# Top_Board_V2.net
KiCad netlist of a schematic drawn in EasyEDA
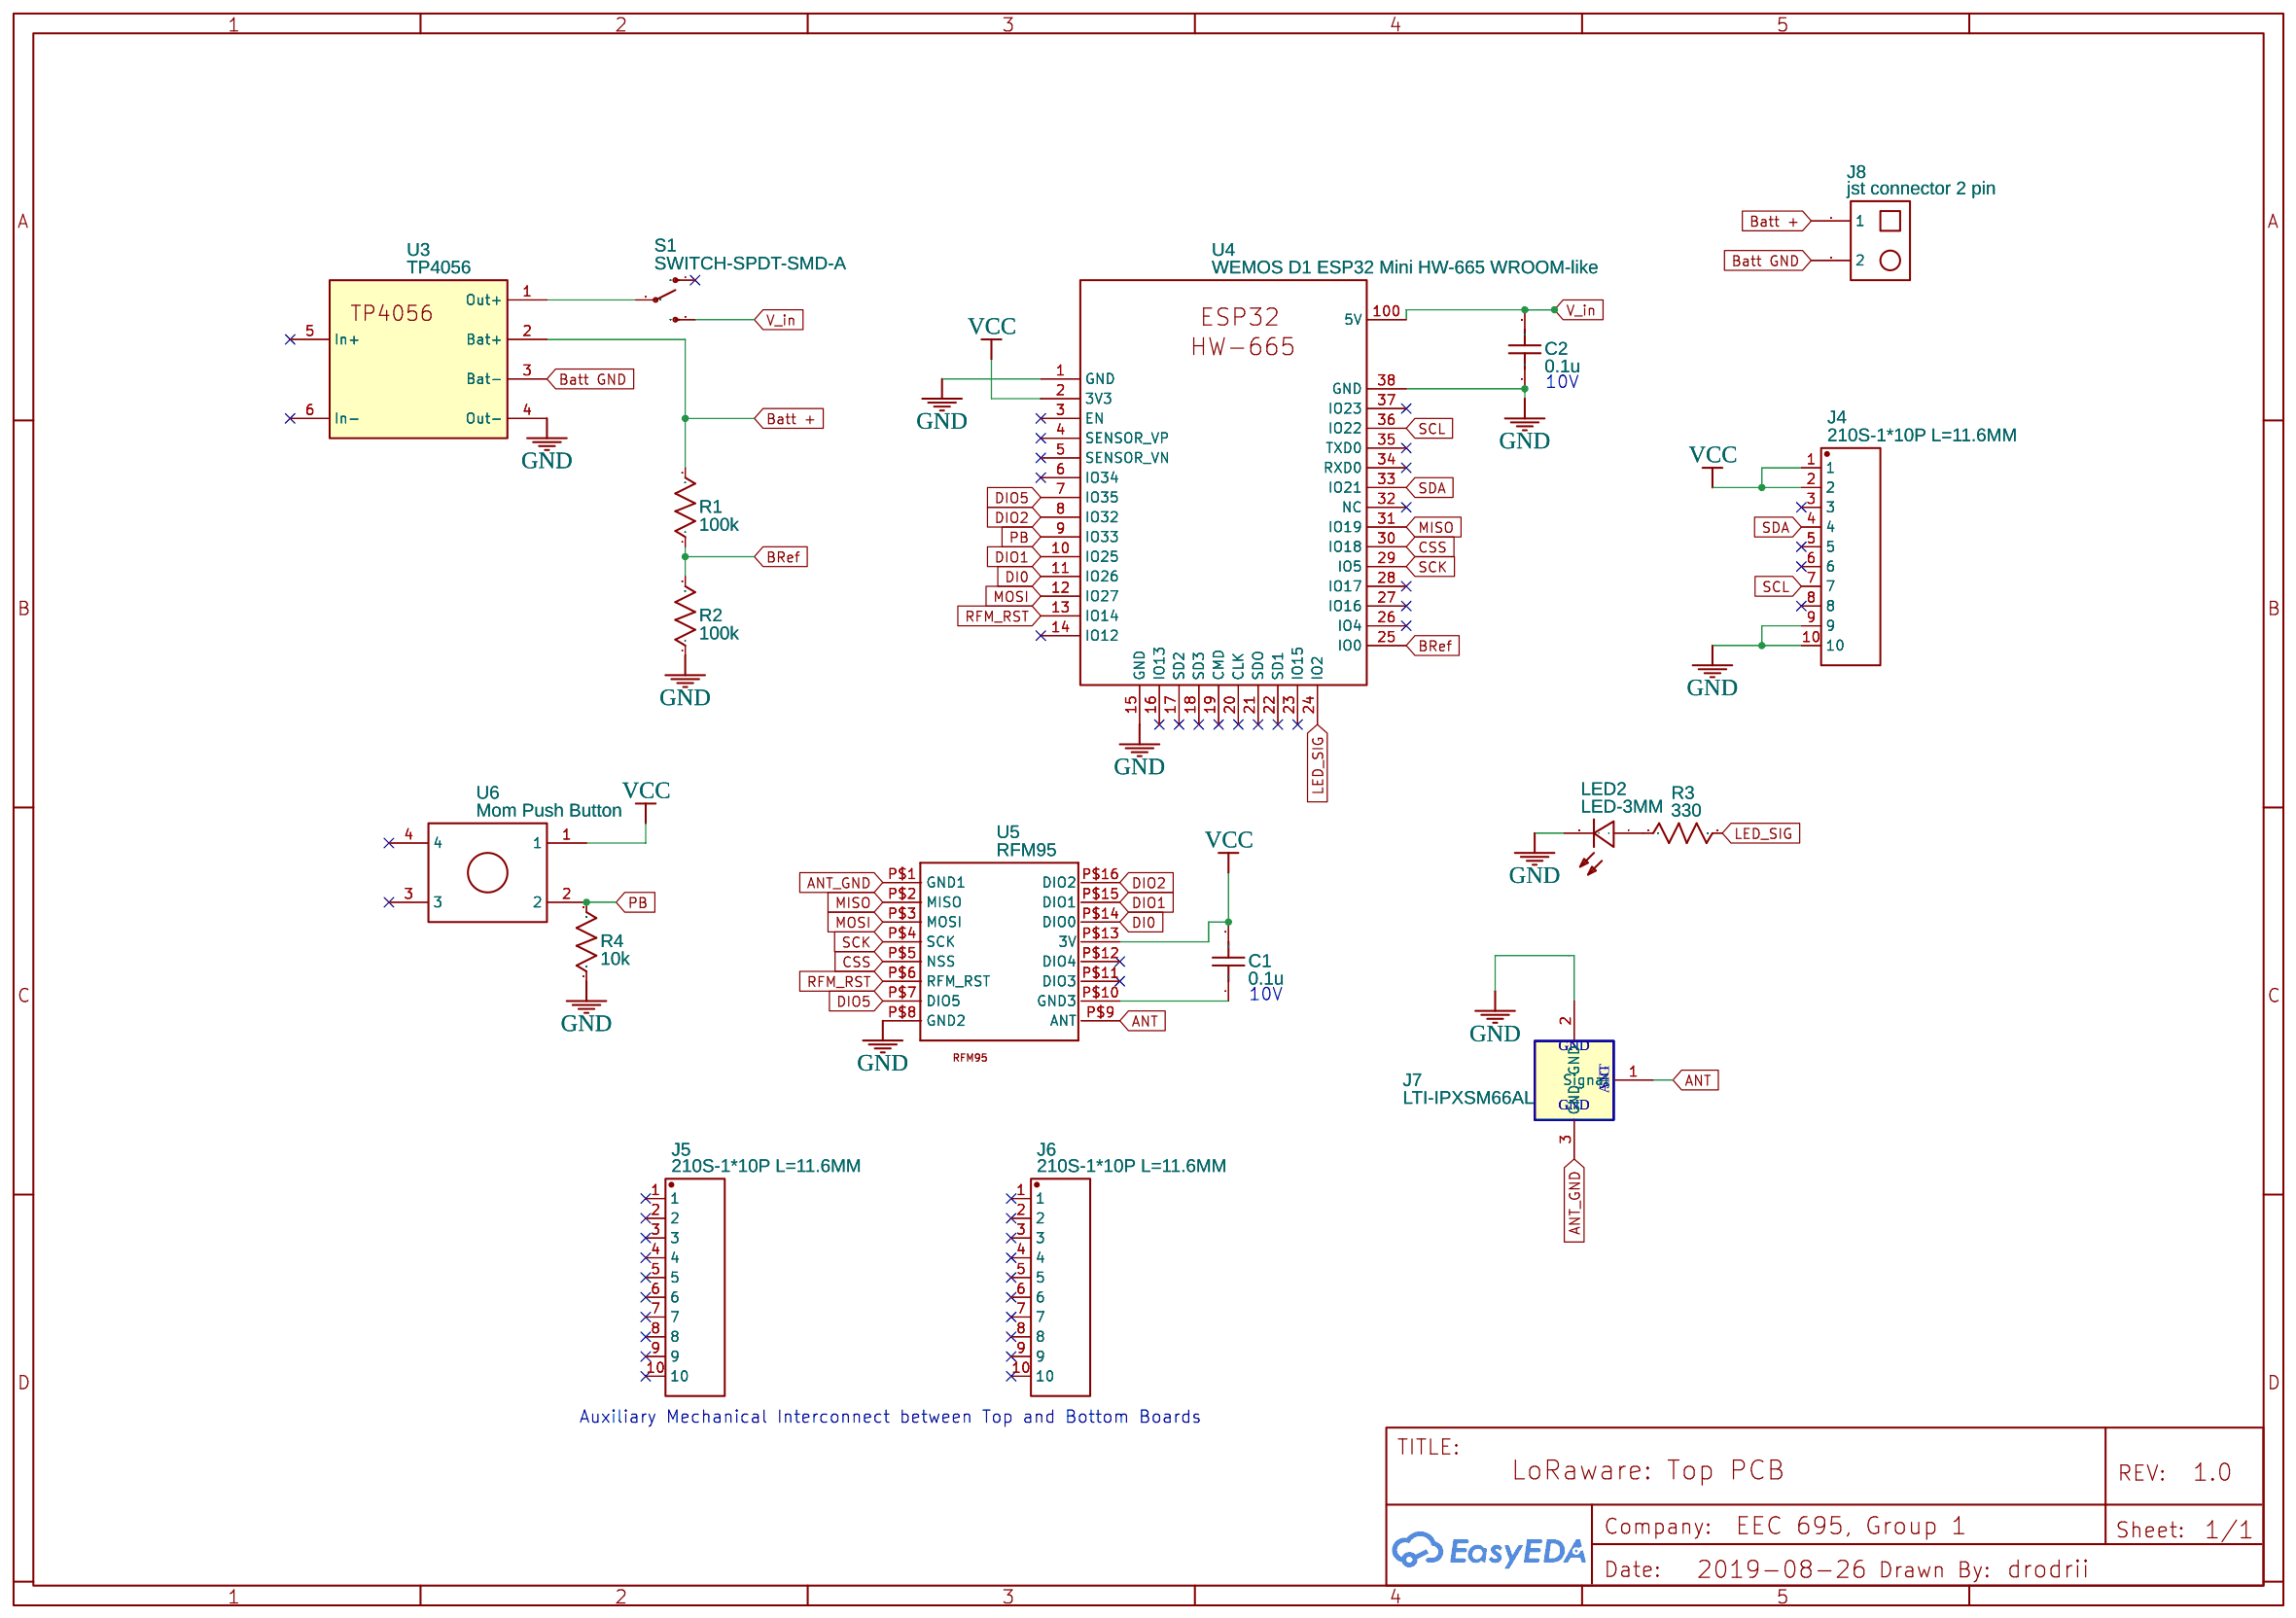
[diagram p0: schematic sheet]

(export (version "E")
  (design (tool "Eeschema 10.0.6"))
  (components
    (comp (ref "C1") (value "0.1u") (libsource (lib "") (part "Cap_0805_US")))
    (comp (ref "C2") (value "0.1u") (libsource (lib "") (part "Cap_0805_US")))
    (comp (ref "J4")
      (value "210S-1*10P L=11.6MM")
      (fields
        (field (name "BOM_Manufacturer Part") "210S-1*10P L=11.6MMGold-plated black")
        (field (name "BOM_Supplier Part") "C124372")
      )
      (libsource (lib "") (part "Unknown_925_275"))
    )
    (comp (ref "J5")
      (value "210S-1*10P L=11.6MM")
      (fields
        (field (name "BOM_Manufacturer Part") "210S-1*10P L=11.6MMGold-plated black")
        (field (name "BOM_Supplier Part") "C124372")
      )
      (libsource (lib "") (part "Unknown_340_645"))
    )
    (comp (ref "J6")
      (value "210S-1*10P L=11.6MM")
      (fields
        (field (name "BOM_Manufacturer Part") "210S-1*10P L=11.6MMGold-plated black")
        (field (name "BOM_Supplier Part") "C124372")
      )
      (libsource (lib "") (part "Unknown_525_645"))
    )
    (comp (ref "J7") (value "LTI-IPXSM66AL") (libsource (lib "") (part "Unknown_790_540")))
    (comp (ref "J8")
      (value "jst connector 2 pin")
      (fields (field (name "BOM_Manufacturer Part") "JST_XH CONNECTOR"))
      (libsource (lib "") (part "Unknown_940_115"))
    )
    (comp (ref "LED2")
      (value "LED-3MM")
      (fields
        (field (name "BOM_Manufacturer Part") "204-10SURD/S530-A3")
        (field (name "BOM_Supplier Part") "C99772")
      )
      (libsource (lib "") (part "Unknown_805_420"))
    )
    (comp (ref "R1")
      (value "100k")
      (fields (field (name "BOM_Manufacturer Part") "?"))
      (libsource (lib "") (part "Res_0805(1/8W)_US_1"))
    )
    (comp (ref "R2")
      (value "100k")
      (fields (field (name "BOM_Manufacturer Part") "?"))
      (libsource (lib "") (part "Res_0805(1/8W)_US_1"))
    )
    (comp (ref "R3")
      (value "330")
      (fields (field (name "BOM_Manufacturer Part") "?"))
      (libsource (lib "") (part "Res_0805(1/8W)_US"))
    )
    (comp (ref "R4")
      (value "10k")
      (fields (field (name "BOM_Manufacturer Part") "?"))
      (libsource (lib "") (part "Res_0805(1/8W)_US_1"))
    )
    (comp (ref "S1")
      (value "SWITCH-SPDT-SMD-A")
      (fields (field (name "BOM_Manufacturer Part") "?"))
      (libsource (lib "") (part "Unknown_330_145"))
    )
    (comp (ref "U3") (value "TP4056") (libsource (lib "") (part "Unknown_160_215")))
    (comp (ref "U4")
      (value "WEMOS D1 ESP32 Mini HW-665 WROOM-like")
      (fields (field (name "BOM_Supplier Part") "WEMOS_D1_ESP32"))
      (libsource (lib "") (part "Unknown_540_325"))
    )
    (comp (ref "U5") (value "RFM95") (libsource (lib "") (part "Unknown_500_485")))
    (comp (ref "U6")
      (value "Mom Push Button")
      (fields (field (name "BOM_Manufacturer Part") "Momentary Push Button"))
      (libsource (lib "") (part "Unknown_270_410"))
    )
  )
  (nets
    (net (code "1") (name "ANT") (class "Default")
      (node (ref "J7") (pin "1") (pinfunction "Signal_1") (pintype "input"))
      (node (ref "U5") (pin "P$9") (pinfunction "ANT_P$9") (pintype "bidirectional"))
    )
    (net (code "2") (name "ANT_GND") (class "Default")
      (node (ref "J7") (pin "3") (pinfunction "GND_3") (pintype "unspecified"))
      (node (ref "U5") (pin "P$1") (pinfunction "GND1_P$1") (pintype "bidirectional"))
    )
    (net (code "3") (name "BRef") (class "Default")
      (node (ref "R1") (pin "1") (pinfunction "1_1") (pintype "unspecified"))
      (node (ref "R2") (pin "2") (pinfunction "2_2") (pintype "unspecified"))
      (node (ref "U4") (pin "25") (pinfunction "IO0_25") (pintype "bidirectional"))
    )
    (net (code "4") (name "Batt +") (class "Default")
      (node (ref "J8") (pin "1") (pinfunction "1_1") (pintype "unspecified"))
      (node (ref "R1") (pin "2") (pinfunction "2_2") (pintype "unspecified"))
      (node (ref "U3") (pin "2") (pinfunction "Bat+_2") (pintype "unspecified"))
    )
    (net (code "5") (name "Batt GND") (class "Default")
      (node (ref "J8") (pin "2") (pinfunction "2_2") (pintype "unspecified"))
      (node (ref "U3") (pin "3") (pinfunction "Bat-_3") (pintype "unspecified"))
    )
    (net (code "6") (name "CSS") (class "Default")
      (node (ref "U4") (pin "30") (pinfunction "IO18_30") (pintype "input"))
      (node (ref "U5") (pin "P$5") (pinfunction "NSS_P$5") (pintype "bidirectional"))
    )
    (net (code "7") (name "DI0") (class "Default")
      (node (ref "U4") (pin "11") (pinfunction "IO26_11") (pintype "bidirectional"))
      (node (ref "U5") (pin "P$14") (pinfunction "DIO0_P$14") (pintype "bidirectional"))
    )
    (net (code "8") (name "DIO1") (class "Default")
      (node (ref "U4") (pin "10") (pinfunction "IO25_10") (pintype "bidirectional"))
      (node (ref "U5") (pin "P$15") (pinfunction "DIO1_P$15") (pintype "bidirectional"))
    )
    (net (code "9") (name "DIO2") (class "Default")
      (node (ref "U4") (pin "8") (pinfunction "IO32_8") (pintype "bidirectional"))
      (node (ref "U5") (pin "P$16") (pinfunction "DIO2_P$16") (pintype "bidirectional"))
    )
    (net (code "10") (name "DIO5") (class "Default")
      (node (ref "U4") (pin "7") (pinfunction "IO35_7") (pintype "bidirectional"))
      (node (ref "U5") (pin "P$7") (pinfunction "DIO5_P$7") (pintype "bidirectional"))
    )
    (net (code "11") (name "GND") (class "Default")
      (node (ref "C2") (pin "1") (pinfunction "1_1") (pintype "unspecified"))
      (node (ref "J4") (pin "10") (pinfunction "10_10") (pintype "unspecified"))
      (node (ref "J4") (pin "9") (pinfunction "9_9") (pintype "unspecified"))
      (node (ref "J7") (pin "2") (pinfunction "GND_2") (pintype "unspecified"))
      (node (ref "LED2") (pin "2") (pinfunction "-_2") (pintype "unspecified"))
      (node (ref "R2") (pin "1") (pinfunction "1_1") (pintype "unspecified"))
      (node (ref "R4") (pin "1") (pinfunction "1_1") (pintype "unspecified"))
      (node (ref "U3") (pin "4") (pinfunction "Out-_4") (pintype "unspecified"))
      (node (ref "U4") (pin "1") (pinfunction "GND_1") (pintype "bidirectional"))
      (node (ref "U4") (pin "15") (pinfunction "GND_15") (pintype "bidirectional"))
      (node (ref "U4") (pin "38") (pinfunction "GND_38") (pintype "bidirectional"))
      (node (ref "U5") (pin "P$8") (pinfunction "GND2_P$8") (pintype "bidirectional"))
    )
    (net (code "12") (name "LED_SIG") (class "Default")
      (node (ref "R3") (pin "2") (pinfunction "2_2") (pintype "unspecified"))
      (node (ref "U4") (pin "24") (pinfunction "IO2_24") (pintype "bidirectional"))
    )
    (net (code "13") (name "MISO") (class "Default")
      (node (ref "U4") (pin "31") (pinfunction "IO19_31") (pintype "bidirectional"))
      (node (ref "U5") (pin "P$2") (pinfunction "MISO_P$2") (pintype "bidirectional"))
    )
    (net (code "14") (name "MOSI") (class "Default")
      (node (ref "U4") (pin "12") (pinfunction "IO27_12") (pintype "bidirectional"))
      (node (ref "U5") (pin "P$3") (pinfunction "MOSI_P$3") (pintype "bidirectional"))
    )
    (net (code "15") (name "Net-(LED2-+)") (class "Default")
      (node (ref "LED2") (pin "1") (pinfunction "+_1") (pintype "unspecified"))
      (node (ref "R3") (pin "1") (pinfunction "1_1") (pintype "unspecified"))
    )
    (net (code "16") (name "Net-(S1-P)") (class "Default")
      (node (ref "S1") (pin "2") (pinfunction "P_2") (pintype "unspecified"))
      (node (ref "U3") (pin "1") (pinfunction "Out+_1") (pintype "unspecified"))
    )
    (net (code "17") (name "Net-(U5-GND3)") (class "Default")
      (node (ref "C1") (pin "1") (pinfunction "1_1") (pintype "unspecified"))
      (node (ref "U5") (pin "P$10") (pinfunction "GND3_P$10") (pintype "bidirectional"))
    )
    (net (code "18") (name "PB") (class "Default")
      (node (ref "R4") (pin "2") (pinfunction "2_2") (pintype "unspecified"))
      (node (ref "U4") (pin "9") (pinfunction "IO33_9") (pintype "bidirectional"))
      (node (ref "U6") (pin "2") (pinfunction "2_2") (pintype "unspecified"))
    )
    (net (code "19") (name "RFM_RST") (class "Default")
      (node (ref "U4") (pin "13") (pinfunction "IO14_13") (pintype "bidirectional"))
      (node (ref "U5") (pin "P$6") (pinfunction "RFM_RST_P$6") (pintype "bidirectional"))
    )
    (net (code "20") (name "SCK") (class "Default")
      (node (ref "U4") (pin "29") (pinfunction "IO5_29") (pintype "bidirectional"))
      (node (ref "U5") (pin "P$4") (pinfunction "SCK_P$4") (pintype "bidirectional"))
    )
    (net (code "21") (name "SCL") (class "Default")
      (node (ref "J4") (pin "7") (pinfunction "7_7") (pintype "unspecified"))
      (node (ref "U4") (pin "36") (pinfunction "IO22_36") (pintype "bidirectional"))
    )
    (net (code "22") (name "SDA") (class "Default")
      (node (ref "J4") (pin "4") (pinfunction "4_4") (pintype "unspecified"))
      (node (ref "U4") (pin "33") (pinfunction "IO21_33") (pintype "bidirectional"))
    )
    (net (code "23") (name "VCC") (class "Default")
      (node (ref "C1") (pin "2") (pinfunction "2_2") (pintype "unspecified"))
      (node (ref "J4") (pin "1") (pinfunction "1_1") (pintype "unspecified"))
      (node (ref "J4") (pin "2") (pinfunction "2_2") (pintype "unspecified"))
      (node (ref "U4") (pin "2") (pinfunction "3V3_2") (pintype "bidirectional"))
      (node (ref "U5") (pin "P$13") (pinfunction "3V_P$13") (pintype "bidirectional"))
      (node (ref "U6") (pin "1") (pinfunction "1_1") (pintype "unspecified"))
    )
    (net (code "24") (name "V_in") (class "Default")
      (node (ref "C2") (pin "2") (pinfunction "2_2") (pintype "unspecified"))
      (node (ref "S1") (pin "3") (pinfunction "S_3") (pintype "unspecified"))
      (node (ref "U4") (pin "100") (pinfunction "5V_100") (pintype "bidirectional"))
    )
    (net (code "25") (name "unconnected-(J4-Pad3)") (class "Default")
      (node (ref "J4") (pin "3") (pinfunction "3_3") (pintype "unspecified+no_connect"))
    )
    (net (code "26") (name "unconnected-(J4-Pad5)") (class "Default")
      (node (ref "J4") (pin "5") (pinfunction "5_5") (pintype "unspecified+no_connect"))
    )
    (net (code "27") (name "unconnected-(J4-Pad6)") (class "Default")
      (node (ref "J4") (pin "6") (pinfunction "6_6") (pintype "unspecified+no_connect"))
    )
    (net (code "28") (name "unconnected-(J4-Pad8)") (class "Default")
      (node (ref "J4") (pin "8") (pinfunction "8_8") (pintype "unspecified+no_connect"))
    )
    (net (code "29") (name "unconnected-(J5-Pad1)") (class "Default")
      (node (ref "J5") (pin "1") (pinfunction "1_1") (pintype "unspecified+no_connect"))
    )
    (net (code "30") (name "unconnected-(J5-Pad2)") (class "Default")
      (node (ref "J5") (pin "2") (pinfunction "2_2") (pintype "unspecified+no_connect"))
    )
    (net (code "31") (name "unconnected-(J5-Pad3)") (class "Default")
      (node (ref "J5") (pin "3") (pinfunction "3_3") (pintype "unspecified+no_connect"))
    )
    (net (code "32") (name "unconnected-(J5-Pad4)") (class "Default")
      (node (ref "J5") (pin "4") (pinfunction "4_4") (pintype "unspecified+no_connect"))
    )
    (net (code "33") (name "unconnected-(J5-Pad5)") (class "Default")
      (node (ref "J5") (pin "5") (pinfunction "5_5") (pintype "unspecified+no_connect"))
    )
    (net (code "34") (name "unconnected-(J5-Pad6)") (class "Default")
      (node (ref "J5") (pin "6") (pinfunction "6_6") (pintype "unspecified+no_connect"))
    )
    (net (code "35") (name "unconnected-(J5-Pad7)") (class "Default")
      (node (ref "J5") (pin "7") (pinfunction "7_7") (pintype "unspecified+no_connect"))
    )
    (net (code "36") (name "unconnected-(J5-Pad8)") (class "Default")
      (node (ref "J5") (pin "8") (pinfunction "8_8") (pintype "unspecified+no_connect"))
    )
    (net (code "37") (name "unconnected-(J5-Pad9)") (class "Default")
      (node (ref "J5") (pin "9") (pinfunction "9_9") (pintype "unspecified+no_connect"))
    )
    (net (code "38") (name "unconnected-(J5-Pad10)") (class "Default")
      (node (ref "J5") (pin "10") (pinfunction "10_10") (pintype "unspecified+no_connect"))
    )
    (net (code "39") (name "unconnected-(J6-Pad1)") (class "Default")
      (node (ref "J6") (pin "1") (pinfunction "1_1") (pintype "unspecified+no_connect"))
    )
    (net (code "40") (name "unconnected-(J6-Pad2)") (class "Default")
      (node (ref "J6") (pin "2") (pinfunction "2_2") (pintype "unspecified+no_connect"))
    )
    (net (code "41") (name "unconnected-(J6-Pad3)") (class "Default")
      (node (ref "J6") (pin "3") (pinfunction "3_3") (pintype "unspecified+no_connect"))
    )
    (net (code "42") (name "unconnected-(J6-Pad4)") (class "Default")
      (node (ref "J6") (pin "4") (pinfunction "4_4") (pintype "unspecified+no_connect"))
    )
    (net (code "43") (name "unconnected-(J6-Pad5)") (class "Default")
      (node (ref "J6") (pin "5") (pinfunction "5_5") (pintype "unspecified+no_connect"))
    )
    (net (code "44") (name "unconnected-(J6-Pad6)") (class "Default")
      (node (ref "J6") (pin "6") (pinfunction "6_6") (pintype "unspecified+no_connect"))
    )
    (net (code "45") (name "unconnected-(J6-Pad7)") (class "Default")
      (node (ref "J6") (pin "7") (pinfunction "7_7") (pintype "unspecified+no_connect"))
    )
    (net (code "46") (name "unconnected-(J6-Pad8)") (class "Default")
      (node (ref "J6") (pin "8") (pinfunction "8_8") (pintype "unspecified+no_connect"))
    )
    (net (code "47") (name "unconnected-(J6-Pad9)") (class "Default")
      (node (ref "J6") (pin "9") (pinfunction "9_9") (pintype "unspecified+no_connect"))
    )
    (net (code "48") (name "unconnected-(J6-Pad10)") (class "Default")
      (node (ref "J6") (pin "10") (pinfunction "10_10") (pintype "unspecified+no_connect"))
    )
    (net (code "49") (name "unconnected-(S1-O-Pad1)") (class "Default")
      (node (ref "S1") (pin "1") (pinfunction "O_1") (pintype "unspecified+no_connect"))
    )
    (net (code "50") (name "unconnected-(U3-In+-Pad5)") (class "Default")
      (node (ref "U3") (pin "5") (pinfunction "In+_5") (pintype "unspecified+no_connect"))
    )
    (net (code "51") (name "unconnected-(U3-In--Pad6)") (class "Default")
      (node (ref "U3") (pin "6") (pinfunction "In-_6") (pintype "unspecified+no_connect"))
    )
    (net (code "52") (name "unconnected-(U4-CLK-Pad20)") (class "Default")
      (node (ref "U4") (pin "20") (pinfunction "CLK_20") (pintype "input+no_connect"))
    )
    (net (code "53") (name "unconnected-(U4-CMD-Pad19)") (class "Default")
      (node (ref "U4") (pin "19") (pinfunction "CMD_19") (pintype "bidirectional+no_connect"))
    )
    (net (code "54") (name "unconnected-(U4-EN-Pad3)") (class "Default")
      (node (ref "U4") (pin "3") (pinfunction "EN_3") (pintype "input+no_connect"))
    )
    (net (code "55") (name "unconnected-(U4-IO4-Pad26)") (class "Default")
      (node (ref "U4") (pin "26") (pinfunction "IO4_26") (pintype "input+no_connect"))
    )
    (net (code "56") (name "unconnected-(U4-IO12-Pad14)") (class "Default")
      (node (ref "U4") (pin "14") (pinfunction "IO12_14") (pintype "bidirectional+no_connect"))
    )
    (net (code "57") (name "unconnected-(U4-IO13-Pad16)") (class "Default")
      (node (ref "U4") (pin "16") (pinfunction "IO13_16") (pintype "bidirectional+no_connect"))
    )
    (net (code "58") (name "unconnected-(U4-IO15-Pad23)") (class "Default")
      (node (ref "U4") (pin "23") (pinfunction "IO15_23") (pintype "bidirectional+no_connect"))
    )
    (net (code "59") (name "unconnected-(U4-IO16-Pad27)") (class "Default")
      (node (ref "U4") (pin "27") (pinfunction "IO16_27") (pintype "bidirectional+no_connect"))
    )
    (net (code "60") (name "unconnected-(U4-IO17-Pad28)") (class "Default")
      (node (ref "U4") (pin "28") (pinfunction "IO17_28") (pintype "bidirectional+no_connect"))
    )
    (net (code "61") (name "unconnected-(U4-IO23-Pad37)") (class "Default")
      (node (ref "U4") (pin "37") (pinfunction "IO23_37") (pintype "bidirectional+no_connect"))
    )
    (net (code "62") (name "unconnected-(U4-IO34-Pad6)") (class "Default")
      (node (ref "U4") (pin "6") (pinfunction "IO34_6") (pintype "bidirectional+no_connect"))
    )
    (net (code "63") (name "unconnected-(U4-NC-Pad32)") (class "Default")
      (node (ref "U4") (pin "32") (pinfunction "NC_32") (pintype "bidirectional+no_connect"))
    )
    (net (code "64") (name "unconnected-(U4-RXD0-Pad34)") (class "Default")
      (node (ref "U4") (pin "34") (pinfunction "RXD0_34") (pintype "bidirectional+no_connect"))
    )
    (net (code "65") (name "unconnected-(U4-SD1-Pad22)") (class "Default")
      (node (ref "U4") (pin "22") (pinfunction "SD1_22") (pintype "bidirectional+no_connect"))
    )
    (net (code "66") (name "unconnected-(U4-SD2-Pad17)") (class "Default")
      (node (ref "U4") (pin "17") (pinfunction "SD2_17") (pintype "bidirectional+no_connect"))
    )
    (net (code "67") (name "unconnected-(U4-SD3-Pad18)") (class "Default")
      (node (ref "U4") (pin "18") (pinfunction "SD3_18") (pintype "bidirectional+no_connect"))
    )
    (net (code "68") (name "unconnected-(U4-SDO-Pad21)") (class "Default")
      (node (ref "U4") (pin "21") (pinfunction "SDO_21") (pintype "bidirectional+no_connect"))
    )
    (net (code "69") (name "unconnected-(U4-SENSOR_VN-Pad5)") (class "Default")
      (node (ref "U4") (pin "5") (pinfunction "SENSOR_VN_5") (pintype "input+no_connect"))
    )
    (net (code "70") (name "unconnected-(U4-SENSOR_VP-Pad4)") (class "Default")
      (node (ref "U4") (pin "4") (pinfunction "SENSOR_VP_4") (pintype "input+no_connect"))
    )
    (net (code "71") (name "unconnected-(U4-TXD0-Pad35)") (class "Default")
      (node (ref "U4") (pin "35") (pinfunction "TXD0_35") (pintype "bidirectional+no_connect"))
    )
    (net (code "72") (name "unconnected-(U5-DIO3-PadP$11)") (class "Default")
      (node (ref "U5") (pin "P$11") (pinfunction "DIO3_P$11") (pintype "bidirectional+no_connect"))
    )
    (net (code "73") (name "unconnected-(U5-DIO4-PadP$12)") (class "Default")
      (node (ref "U5") (pin "P$12") (pinfunction "DIO4_P$12") (pintype "bidirectional+no_connect"))
    )
    (net (code "74") (name "unconnected-(U6-Pad3)") (class "Default")
      (node (ref "U6") (pin "3") (pinfunction "3_3") (pintype "unspecified+no_connect"))
    )
    (net (code "75") (name "unconnected-(U6-Pad4)") (class "Default")
      (node (ref "U6") (pin "4") (pinfunction "4_4") (pintype "unspecified+no_connect"))
    )
  )
)
